# open-V2.net
KiCad netlist of a schematic drawn in EAGLE
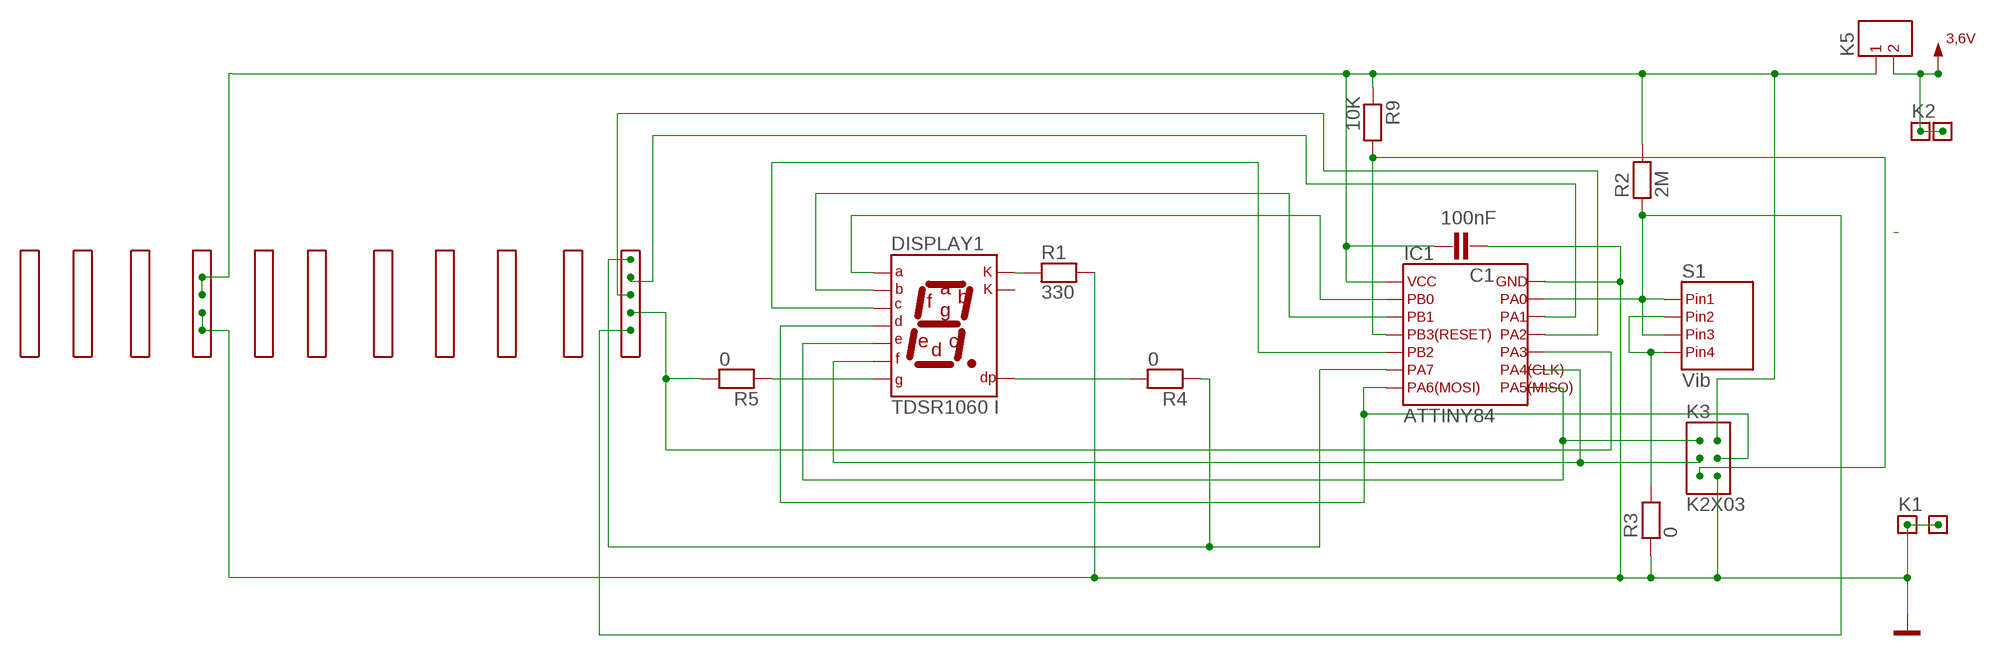
[diagram p0: schematic, sheet 1]

(export (version "E")
  (design (tool "Eeschema 10.0.6"))
  (components
    (comp (ref "C1")
      (value "100nF")
      (footprint "eagle-import:C1")
      (libsource (lib "eagle-import") (part "C1"))
    )
    (comp (ref "DISPLAY1")
      (value "TDSR1060 I")
      (footprint "eagle-import:DISPLAY1")
      (libsource (lib "eagle-import") (part "DISPLAY1"))
    )
    (comp (ref "IC1")
      (value "ATTINY84")
      (footprint "eagle-import:IC1")
      (libsource (lib "eagle-import") (part "IC1"))
    )
    (comp (ref "K1") (value "K1") (footprint "eagle-import:K1") (libsource (lib "eagle-import") (part "K1")))
    (comp (ref "K2") (value "K2") (footprint "eagle-import:K2") (libsource (lib "eagle-import") (part "K2")))
    (comp (ref "K3")
      (value "K2X03")
      (footprint "eagle-import:K3")
      (libsource (lib "eagle-import") (part "K3"))
    )
    (comp (ref "K4") (value "K4") (footprint "eagle-import:K4") (libsource (lib "eagle-import") (part "K4")))
    (comp (ref "K5") (value "K5") (footprint "eagle-import:K5") (libsource (lib "eagle-import") (part "K5")))
    (comp (ref "K6") (value "K6") (footprint "eagle-import:K6") (libsource (lib "eagle-import") (part "K6")))
    (comp (ref "K7") (value "K7") (footprint "eagle-import:K7") (libsource (lib "eagle-import") (part "K7")))
    (comp (ref "K8") (value "K8") (footprint "eagle-import:K8") (libsource (lib "eagle-import") (part "K8")))
    (comp (ref "K9") (value "K9") (footprint "eagle-import:K9") (libsource (lib "eagle-import") (part "K9")))
    (comp (ref "K10")
      (value "K10")
      (footprint "eagle-import:K10")
      (libsource (lib "eagle-import") (part "K10"))
    )
    (comp (ref "K11")
      (value "K11")
      (footprint "eagle-import:K11")
      (libsource (lib "eagle-import") (part "K11"))
    )
    (comp (ref "K12")
      (value "K12")
      (footprint "eagle-import:K12")
      (libsource (lib "eagle-import") (part "K12"))
    )
    (comp (ref "K13")
      (value "K13")
      (footprint "eagle-import:K13")
      (libsource (lib "eagle-import") (part "K13"))
    )
    (comp (ref "K14")
      (value "K14")
      (footprint "eagle-import:K14")
      (libsource (lib "eagle-import") (part "K14"))
    )
    (comp (ref "K15")
      (value "K15")
      (footprint "eagle-import:K15")
      (libsource (lib "eagle-import") (part "K15"))
    )
    (comp (ref "K16")
      (value "K16")
      (footprint "eagle-import:K16")
      (libsource (lib "eagle-import") (part "K16"))
    )
    (comp (ref "K18")
      (value "K18")
      (footprint "eagle-import:K18")
      (libsource (lib "eagle-import") (part "K18"))
    )
    (comp (ref "R1") (value "330") (footprint "eagle-import:R1") (libsource (lib "eagle-import") (part "R1")))
    (comp (ref "R2") (value "2M") (footprint "eagle-import:R2") (libsource (lib "eagle-import") (part "R2")))
    (comp (ref "R3") (value "0") (footprint "eagle-import:R3") (libsource (lib "eagle-import") (part "R3")))
    (comp (ref "R4") (value "0") (footprint "eagle-import:R4") (libsource (lib "eagle-import") (part "R4")))
    (comp (ref "R5") (value "0") (footprint "eagle-import:R5") (libsource (lib "eagle-import") (part "R5")))
    (comp (ref "R9") (value "10K") (footprint "eagle-import:R9") (libsource (lib "eagle-import") (part "R9")))
    (comp (ref "S1") (value "Vib") (footprint "eagle-import:S1") (libsource (lib "eagle-import") (part "S1")))
  )
  (nets
    (net (code "1") (name "GND") (class "Default")
      (node (ref "C1") (pin "1") (pinfunction "1_1") (pintype "passive"))
      (node (ref "IC1") (pin "14") (pinfunction "GND_14") (pintype "power_in"))
      (node (ref "K1") (pin "1") (pinfunction "1_1") (pintype "passive"))
      (node (ref "K13") (pin "2") (pinfunction "2_2") (pintype "passive"))
      (node (ref "K13") (pin "3") (pinfunction "3_3") (pintype "passive"))
      (node (ref "K16") (pin "1") (pinfunction "1_1") (pintype "passive"))
      (node (ref "K3") (pin "6") (pinfunction "6_6") (pintype "passive"))
      (node (ref "R1") (pin "2") (pinfunction "2_2") (pintype "passive"))
      (node (ref "R3") (pin "1") (pinfunction "1_1") (pintype "passive"))
    )
    (net (code "2") (name "Net-(DISPLAY1-A)") (class "Default")
      (node (ref "DISPLAY1") (pin "10") (pinfunction "A_10") (pintype "passive"))
      (node (ref "IC1") (pin "2") (pinfunction "PB0_2") (pintype "bidirectional"))
    )
    (net (code "3") (name "Net-(DISPLAY1-B)") (class "Default")
      (node (ref "DISPLAY1") (pin "9") (pinfunction "B_9") (pintype "passive"))
      (node (ref "IC1") (pin "3") (pinfunction "PB1_3") (pintype "bidirectional"))
    )
    (net (code "4") (name "Net-(DISPLAY1-C)") (class "Default")
      (node (ref "DISPLAY1") (pin "7") (pinfunction "C_7") (pintype "passive"))
      (node (ref "IC1") (pin "5") (pinfunction "PB2_5") (pintype "bidirectional"))
    )
    (net (code "5") (name "Net-(DISPLAY1-D)") (class "Default")
      (node (ref "DISPLAY1") (pin "5") (pinfunction "D_5") (pintype "passive"))
      (node (ref "IC1") (pin "7") (pinfunction "PA6(MOSI)_7") (pintype "bidirectional"))
      (node (ref "K3") (pin "4") (pinfunction "4_4") (pintype "passive"))
    )
    (net (code "6") (name "Net-(DISPLAY1-DP)") (class "Default")
      (node (ref "DISPLAY1") (pin "6") (pinfunction "DP_6") (pintype "passive"))
      (node (ref "R4") (pin "2") (pinfunction "2_2") (pintype "passive"))
    )
    (net (code "7") (name "Net-(DISPLAY1-E)") (class "Default")
      (node (ref "DISPLAY1") (pin "4") (pinfunction "E_4") (pintype "passive"))
      (node (ref "IC1") (pin "8") (pinfunction "PA5(MISO)_8") (pintype "bidirectional"))
      (node (ref "K3") (pin "1") (pinfunction "1_1") (pintype "passive"))
    )
    (net (code "8") (name "Net-(DISPLAY1-F)") (class "Default")
      (node (ref "DISPLAY1") (pin "2") (pinfunction "F_2") (pintype "passive"))
      (node (ref "IC1") (pin "9") (pinfunction "PA4(CLK)_9") (pintype "bidirectional"))
      (node (ref "K3") (pin "3") (pinfunction "3_3") (pintype "passive"))
    )
    (net (code "9") (name "Net-(DISPLAY1-G)") (class "Default")
      (node (ref "DISPLAY1") (pin "1") (pinfunction "G_1") (pintype "passive"))
      (node (ref "R5") (pin "1") (pinfunction "1_1") (pintype "passive"))
    )
    (net (code "10") (name "Net-(DISPLAY1-K-Pad3)") (class "Default")
      (node (ref "DISPLAY1") (pin "3") (pinfunction "K_3") (pintype "passive"))
      (node (ref "R1") (pin "1") (pinfunction "1_1") (pintype "passive"))
    )
    (net (code "11") (name "Net-(IC1-PA0)") (class "Default")
      (node (ref "IC1") (pin "13") (pinfunction "PA0_13") (pintype "bidirectional"))
      (node (ref "K10") (pin "2") (pinfunction "2_2") (pintype "passive"))
      (node (ref "R2") (pin "1") (pinfunction "1_1") (pintype "passive"))
      (node (ref "S1") (pin "1") (pinfunction "PIN1_1") (pintype "passive"))
      (node (ref "S1") (pin "3") (pinfunction "PIN3_3") (pintype "passive"))
    )
    (net (code "12") (name "Net-(IC1-PA1)") (class "Default")
      (node (ref "IC1") (pin "12") (pinfunction "PA1_12") (pintype "bidirectional"))
      (node (ref "K10") (pin "5") (pinfunction "5_5") (pintype "passive"))
    )
    (net (code "13") (name "Net-(IC1-PA2)") (class "Default")
      (node (ref "IC1") (pin "11") (pinfunction "PA2_11") (pintype "bidirectional"))
      (node (ref "K10") (pin "4") (pinfunction "4_4") (pintype "passive"))
    )
    (net (code "14") (name "Net-(IC1-PA3)") (class "Default")
      (node (ref "IC1") (pin "10") (pinfunction "PA3_10") (pintype "bidirectional"))
      (node (ref "K10") (pin "3") (pinfunction "3_3") (pintype "passive"))
      (node (ref "R5") (pin "2") (pinfunction "2_2") (pintype "passive"))
    )
    (net (code "15") (name "Net-(IC1-PA7)") (class "Default")
      (node (ref "IC1") (pin "6") (pinfunction "PA7_6") (pintype "bidirectional"))
      (node (ref "K10") (pin "6") (pinfunction "6_6") (pintype "passive"))
      (node (ref "R4") (pin "1") (pinfunction "1_1") (pintype "passive"))
    )
    (net (code "16") (name "Net-(IC1-PB3(RESET))") (class "Default")
      (node (ref "IC1") (pin "4") (pinfunction "PB3(RESET)_4") (pintype "bidirectional"))
      (node (ref "K3") (pin "5") (pinfunction "5_5") (pintype "passive"))
      (node (ref "R9") (pin "2") (pinfunction "2_2") (pintype "passive"))
    )
    (net (code "17") (name "Net-(IC1-VCC)") (class "Default")
      (node (ref "C1") (pin "2") (pinfunction "2_2") (pintype "passive"))
      (node (ref "IC1") (pin "1") (pinfunction "VCC_1") (pintype "power_in"))
      (node (ref "K13") (pin "4") (pinfunction "4_4") (pintype "passive"))
      (node (ref "K13") (pin "5") (pinfunction "5_5") (pintype "passive"))
      (node (ref "K3") (pin "2") (pinfunction "2_2") (pintype "passive"))
      (node (ref "K5") (pin "1") (pinfunction "1_1") (pintype "passive"))
      (node (ref "R2") (pin "2") (pinfunction "2_2") (pintype "passive"))
      (node (ref "R9") (pin "1") (pinfunction "1_1") (pintype "passive"))
    )
    (net (code "18") (name "Net-(S1-PIN2)") (class "Default")
      (node (ref "R3") (pin "2") (pinfunction "2_2") (pintype "passive"))
      (node (ref "S1") (pin "2") (pinfunction "PIN2_2") (pintype "passive"))
      (node (ref "S1") (pin "4") (pinfunction "PIN4_4") (pintype "passive"))
    )
    (net (code "19") (name "VCC_1") (class "Default")
      (node (ref "K18") (pin "1") (pinfunction "1_1") (pintype "passive"))
      (node (ref "K2") (pin "1") (pinfunction "1_1") (pintype "passive"))
      (node (ref "K5") (pin "2") (pinfunction "2_2") (pintype "passive"))
    )
    (net (code "20") (name "unconnected-(DISPLAY1-K-Pad8)") (class "Default")
      (node (ref "DISPLAY1") (pin "8") (pinfunction "K_8") (pintype "passive"))
    )
    (net (code "21") (name "unconnected-(K4-Pad1)") (class "Default")
      (node (ref "K4") (pin "1") (pinfunction "1_1") (pintype "passive"))
    )
    (net (code "22") (name "unconnected-(K4-Pad2)") (class "Default")
      (node (ref "K4") (pin "2") (pinfunction "2_2") (pintype "passive"))
    )
    (net (code "23") (name "unconnected-(K4-Pad3)") (class "Default")
      (node (ref "K4") (pin "3") (pinfunction "3_3") (pintype "passive"))
    )
    (net (code "24") (name "unconnected-(K4-Pad4)") (class "Default")
      (node (ref "K4") (pin "4") (pinfunction "4_4") (pintype "passive"))
    )
    (net (code "25") (name "unconnected-(K4-Pad5)") (class "Default")
      (node (ref "K4") (pin "5") (pinfunction "5_5") (pintype "passive"))
    )
    (net (code "26") (name "unconnected-(K4-Pad6)") (class "Default")
      (node (ref "K4") (pin "6") (pinfunction "6_6") (pintype "passive"))
    )
    (net (code "27") (name "unconnected-(K6-Pad1)") (class "Default")
      (node (ref "K6") (pin "1") (pinfunction "1_1") (pintype "passive"))
    )
    (net (code "28") (name "unconnected-(K6-Pad2)") (class "Default")
      (node (ref "K6") (pin "2") (pinfunction "2_2") (pintype "passive"))
    )
    (net (code "29") (name "unconnected-(K6-Pad3)") (class "Default")
      (node (ref "K6") (pin "3") (pinfunction "3_3") (pintype "passive"))
    )
    (net (code "30") (name "unconnected-(K6-Pad4)") (class "Default")
      (node (ref "K6") (pin "4") (pinfunction "4_4") (pintype "passive"))
    )
    (net (code "31") (name "unconnected-(K6-Pad5)") (class "Default")
      (node (ref "K6") (pin "5") (pinfunction "5_5") (pintype "passive"))
    )
    (net (code "32") (name "unconnected-(K6-Pad6)") (class "Default")
      (node (ref "K6") (pin "6") (pinfunction "6_6") (pintype "passive"))
    )
    (net (code "33") (name "unconnected-(K7-Pad1)") (class "Default")
      (node (ref "K7") (pin "1") (pinfunction "1_1") (pintype "passive"))
    )
    (net (code "34") (name "unconnected-(K7-Pad2)") (class "Default")
      (node (ref "K7") (pin "2") (pinfunction "2_2") (pintype "passive"))
    )
    (net (code "35") (name "unconnected-(K7-Pad3)") (class "Default")
      (node (ref "K7") (pin "3") (pinfunction "3_3") (pintype "passive"))
    )
    (net (code "36") (name "unconnected-(K7-Pad4)") (class "Default")
      (node (ref "K7") (pin "4") (pinfunction "4_4") (pintype "passive"))
    )
    (net (code "37") (name "unconnected-(K7-Pad5)") (class "Default")
      (node (ref "K7") (pin "5") (pinfunction "5_5") (pintype "passive"))
    )
    (net (code "38") (name "unconnected-(K7-Pad6)") (class "Default")
      (node (ref "K7") (pin "6") (pinfunction "6_6") (pintype "passive"))
    )
    (net (code "39") (name "unconnected-(K8-Pad1)") (class "Default")
      (node (ref "K8") (pin "1") (pinfunction "1_1") (pintype "passive"))
    )
    (net (code "40") (name "unconnected-(K8-Pad2)") (class "Default")
      (node (ref "K8") (pin "2") (pinfunction "2_2") (pintype "passive"))
    )
    (net (code "41") (name "unconnected-(K8-Pad3)") (class "Default")
      (node (ref "K8") (pin "3") (pinfunction "3_3") (pintype "passive"))
    )
    (net (code "42") (name "unconnected-(K8-Pad4)") (class "Default")
      (node (ref "K8") (pin "4") (pinfunction "4_4") (pintype "passive"))
    )
    (net (code "43") (name "unconnected-(K8-Pad5)") (class "Default")
      (node (ref "K8") (pin "5") (pinfunction "5_5") (pintype "passive"))
    )
    (net (code "44") (name "unconnected-(K8-Pad6)") (class "Default")
      (node (ref "K8") (pin "6") (pinfunction "6_6") (pintype "passive"))
    )
    (net (code "45") (name "unconnected-(K9-Pad1)") (class "Default")
      (node (ref "K9") (pin "1") (pinfunction "1_1") (pintype "passive"))
    )
    (net (code "46") (name "unconnected-(K9-Pad2)") (class "Default")
      (node (ref "K9") (pin "2") (pinfunction "2_2") (pintype "passive"))
    )
    (net (code "47") (name "unconnected-(K9-Pad3)") (class "Default")
      (node (ref "K9") (pin "3") (pinfunction "3_3") (pintype "passive"))
    )
    (net (code "48") (name "unconnected-(K9-Pad4)") (class "Default")
      (node (ref "K9") (pin "4") (pinfunction "4_4") (pintype "passive"))
    )
    (net (code "49") (name "unconnected-(K9-Pad5)") (class "Default")
      (node (ref "K9") (pin "5") (pinfunction "5_5") (pintype "passive"))
    )
    (net (code "50") (name "unconnected-(K9-Pad6)") (class "Default")
      (node (ref "K9") (pin "6") (pinfunction "6_6") (pintype "passive"))
    )
    (net (code "51") (name "unconnected-(K10-Pad1)") (class "Default")
      (node (ref "K10") (pin "1") (pinfunction "1_1") (pintype "passive"))
    )
    (net (code "52") (name "unconnected-(K11-Pad1)") (class "Default")
      (node (ref "K11") (pin "1") (pinfunction "1_1") (pintype "passive"))
    )
    (net (code "53") (name "unconnected-(K11-Pad2)") (class "Default")
      (node (ref "K11") (pin "2") (pinfunction "2_2") (pintype "passive"))
    )
    (net (code "54") (name "unconnected-(K11-Pad3)") (class "Default")
      (node (ref "K11") (pin "3") (pinfunction "3_3") (pintype "passive"))
    )
    (net (code "55") (name "unconnected-(K11-Pad4)") (class "Default")
      (node (ref "K11") (pin "4") (pinfunction "4_4") (pintype "passive"))
    )
    (net (code "56") (name "unconnected-(K11-Pad5)") (class "Default")
      (node (ref "K11") (pin "5") (pinfunction "5_5") (pintype "passive"))
    )
    (net (code "57") (name "unconnected-(K11-Pad6)") (class "Default")
      (node (ref "K11") (pin "6") (pinfunction "6_6") (pintype "passive"))
    )
    (net (code "58") (name "unconnected-(K12-Pad1)") (class "Default")
      (node (ref "K12") (pin "1") (pinfunction "1_1") (pintype "passive"))
    )
    (net (code "59") (name "unconnected-(K12-Pad2)") (class "Default")
      (node (ref "K12") (pin "2") (pinfunction "2_2") (pintype "passive"))
    )
    (net (code "60") (name "unconnected-(K12-Pad3)") (class "Default")
      (node (ref "K12") (pin "3") (pinfunction "3_3") (pintype "passive"))
    )
    (net (code "61") (name "unconnected-(K12-Pad4)") (class "Default")
      (node (ref "K12") (pin "4") (pinfunction "4_4") (pintype "passive"))
    )
    (net (code "62") (name "unconnected-(K12-Pad5)") (class "Default")
      (node (ref "K12") (pin "5") (pinfunction "5_5") (pintype "passive"))
    )
    (net (code "63") (name "unconnected-(K12-Pad6)") (class "Default")
      (node (ref "K12") (pin "6") (pinfunction "6_6") (pintype "passive"))
    )
    (net (code "64") (name "unconnected-(K13-Pad1)") (class "Default")
      (node (ref "K13") (pin "1") (pinfunction "1_1") (pintype "passive"))
    )
    (net (code "65") (name "unconnected-(K13-Pad6)") (class "Default")
      (node (ref "K13") (pin "6") (pinfunction "6_6") (pintype "passive"))
    )
    (net (code "66") (name "unconnected-(K14-Pad1)") (class "Default")
      (node (ref "K14") (pin "1") (pinfunction "1_1") (pintype "passive"))
    )
    (net (code "67") (name "unconnected-(K14-Pad2)") (class "Default")
      (node (ref "K14") (pin "2") (pinfunction "2_2") (pintype "passive"))
    )
    (net (code "68") (name "unconnected-(K14-Pad3)") (class "Default")
      (node (ref "K14") (pin "3") (pinfunction "3_3") (pintype "passive"))
    )
    (net (code "69") (name "unconnected-(K14-Pad4)") (class "Default")
      (node (ref "K14") (pin "4") (pinfunction "4_4") (pintype "passive"))
    )
    (net (code "70") (name "unconnected-(K14-Pad5)") (class "Default")
      (node (ref "K14") (pin "5") (pinfunction "5_5") (pintype "passive"))
    )
    (net (code "71") (name "unconnected-(K14-Pad6)") (class "Default")
      (node (ref "K14") (pin "6") (pinfunction "6_6") (pintype "passive"))
    )
    (net (code "72") (name "unconnected-(K15-Pad1)") (class "Default")
      (node (ref "K15") (pin "1") (pinfunction "1_1") (pintype "passive"))
    )
    (net (code "73") (name "unconnected-(K15-Pad2)") (class "Default")
      (node (ref "K15") (pin "2") (pinfunction "2_2") (pintype "passive"))
    )
    (net (code "74") (name "unconnected-(K15-Pad3)") (class "Default")
      (node (ref "K15") (pin "3") (pinfunction "3_3") (pintype "passive"))
    )
    (net (code "75") (name "unconnected-(K15-Pad4)") (class "Default")
      (node (ref "K15") (pin "4") (pinfunction "4_4") (pintype "passive"))
    )
    (net (code "76") (name "unconnected-(K15-Pad5)") (class "Default")
      (node (ref "K15") (pin "5") (pinfunction "5_5") (pintype "passive"))
    )
    (net (code "77") (name "unconnected-(K15-Pad6)") (class "Default")
      (node (ref "K15") (pin "6") (pinfunction "6_6") (pintype "passive"))
    )
  )
)
